# Power_Up_4_0.net
KiCad netlist of a schematic drawn in EAGLE
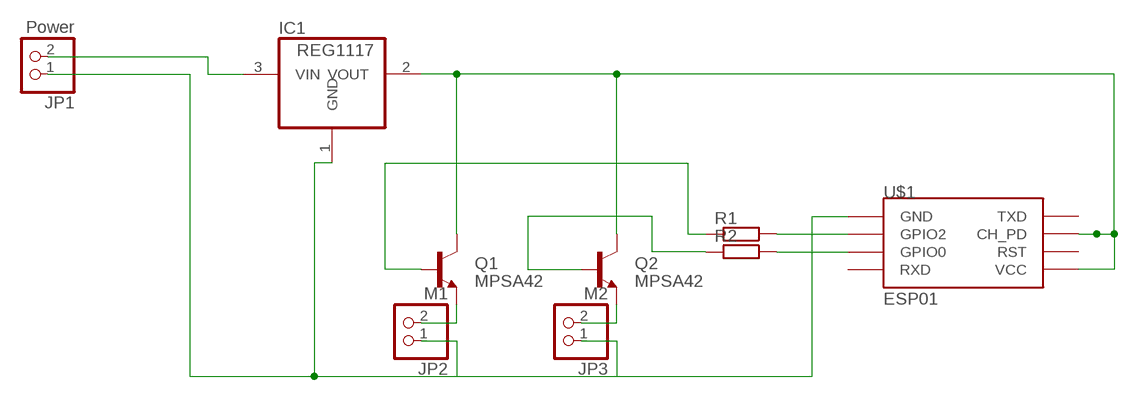
[diagram p0: schematic, sheet 1]

(export (version "E")
  (design (tool "Eeschema 10.0.6"))
  (components
    (comp (ref "IC1")
      (value "REG1117")
      (footprint "eagle-import:SOT223")
      (libsource (lib "eagle-import") (part "REG1117"))
    )
    (comp (ref "JP1")
      (value "Power")
      (footprint "eagle-import:1X02")
      (libsource (lib "eagle-import") (part "PINHD-1X2"))
    )
    (comp (ref "JP2")
      (value "M1")
      (footprint "eagle-import:1X02")
      (libsource (lib "eagle-import") (part "PINHD-1X2"))
    )
    (comp (ref "JP3")
      (value "M2")
      (footprint "eagle-import:1X02")
      (libsource (lib "eagle-import") (part "PINHD-1X2"))
    )
    (comp (ref "Q1")
      (value "MPSA42")
      (footprint "eagle-import:SOT23-3")
      (libsource (lib "eagle-import") (part "TRANSISTOR_NPNMPSA42"))
    )
    (comp (ref "Q2")
      (value "MPSA42")
      (footprint "eagle-import:SOT23-3")
      (libsource (lib "eagle-import") (part "TRANSISTOR_NPNMPSA42"))
    )
    (comp (ref "R1")
      (value "SMR-WAV")
      (footprint "eagle-import:SMS-WAV")
      (libsource (lib "eagle-import") (part "SMR-WAV"))
    )
    (comp (ref "R2")
      (value "SMR-WAV")
      (footprint "eagle-import:SMS-WAV")
      (libsource (lib "eagle-import") (part "SMR-WAV"))
    )
    (comp (ref "U$1")
      (value "ESP01")
      (footprint "eagle-import:ESP01")
      (libsource (lib "eagle-import") (part "ESP01"))
    )
  )
  (nets
    (net (code "1") (name "Net-(IC1-GND)") (class "Default")
      (node (ref "IC1") (pin "1") (pinfunction "GND_1") (pintype "power_in"))
      (node (ref "JP1") (pin "1") (pinfunction "1_1") (pintype "passive"))
      (node (ref "JP2") (pin "1") (pinfunction "1_1") (pintype "passive"))
      (node (ref "JP3") (pin "1") (pinfunction "1_1") (pintype "passive"))
      (node (ref "U$1") (pin "GND") (pinfunction "GND_GND") (pintype "bidirectional"))
    )
    (net (code "2") (name "Net-(IC1-VIN)") (class "Default")
      (node (ref "IC1") (pin "3") (pinfunction "VIN_3") (pintype "input"))
      (node (ref "JP1") (pin "2") (pinfunction "2_2") (pintype "passive"))
    )
    (net (code "3") (name "Net-(IC1-VOUT)") (class "Default")
      (node (ref "IC1") (pin "2") (pinfunction "VOUT_2") (pintype "output"))
      (node (ref "Q1") (pin "3") (pinfunction "C_3") (pintype "passive"))
      (node (ref "Q2") (pin "3") (pinfunction "C_3") (pintype "passive"))
      (node (ref "U$1") (pin "CH_PD") (pinfunction "CH_PD_CH_PD") (pintype "bidirectional"))
      (node (ref "U$1") (pin "VCC") (pinfunction "VCC_VCC") (pintype "bidirectional"))
    )
    (net (code "4") (name "Net-(Q1-B)") (class "Default")
      (node (ref "Q1") (pin "1") (pinfunction "B_1") (pintype "passive"))
      (node (ref "R1") (pin "2") (pinfunction "2_2") (pintype "passive"))
    )
    (net (code "5") (name "Net-(Q1-E)") (class "Default")
      (node (ref "JP2") (pin "2") (pinfunction "2_2") (pintype "passive"))
      (node (ref "Q1") (pin "2") (pinfunction "E_2") (pintype "passive"))
    )
    (net (code "6") (name "Net-(Q2-B)") (class "Default")
      (node (ref "Q2") (pin "1") (pinfunction "B_1") (pintype "passive"))
      (node (ref "R2") (pin "2") (pinfunction "2_2") (pintype "passive"))
    )
    (net (code "7") (name "Net-(Q2-E)") (class "Default")
      (node (ref "JP3") (pin "2") (pinfunction "2_2") (pintype "passive"))
      (node (ref "Q2") (pin "2") (pinfunction "E_2") (pintype "passive"))
    )
    (net (code "8") (name "Net-(R1-Pad1)") (class "Default")
      (node (ref "R1") (pin "1") (pinfunction "1_1") (pintype "passive"))
      (node (ref "U$1") (pin "GPIO2") (pinfunction "GPIO2_GPIO2") (pintype "bidirectional"))
    )
    (net (code "9") (name "Net-(R2-Pad1)") (class "Default")
      (node (ref "R2") (pin "1") (pinfunction "1_1") (pintype "passive"))
      (node (ref "U$1") (pin "GPIO0") (pinfunction "GPIO0_GPIO0") (pintype "bidirectional"))
    )
    (net (code "10") (name "unconnected-(U$1-PadRST)") (class "Default")
      (node (ref "U$1") (pin "RST") (pinfunction "RST_RST") (pintype "bidirectional"))
    )
    (net (code "11") (name "unconnected-(U$1-RXD-PadRX)") (class "Default")
      (node (ref "U$1") (pin "RX") (pinfunction "RXD_RX") (pintype "bidirectional"))
    )
    (net (code "12") (name "unconnected-(U$1-TXD-PadTX)") (class "Default")
      (node (ref "U$1") (pin "TX") (pinfunction "TXD_TX") (pintype "bidirectional"))
    )
  )
)
